# 2015_AlimBeaconEye.net
KiCad netlist of a schematic drawn in Altium Designer
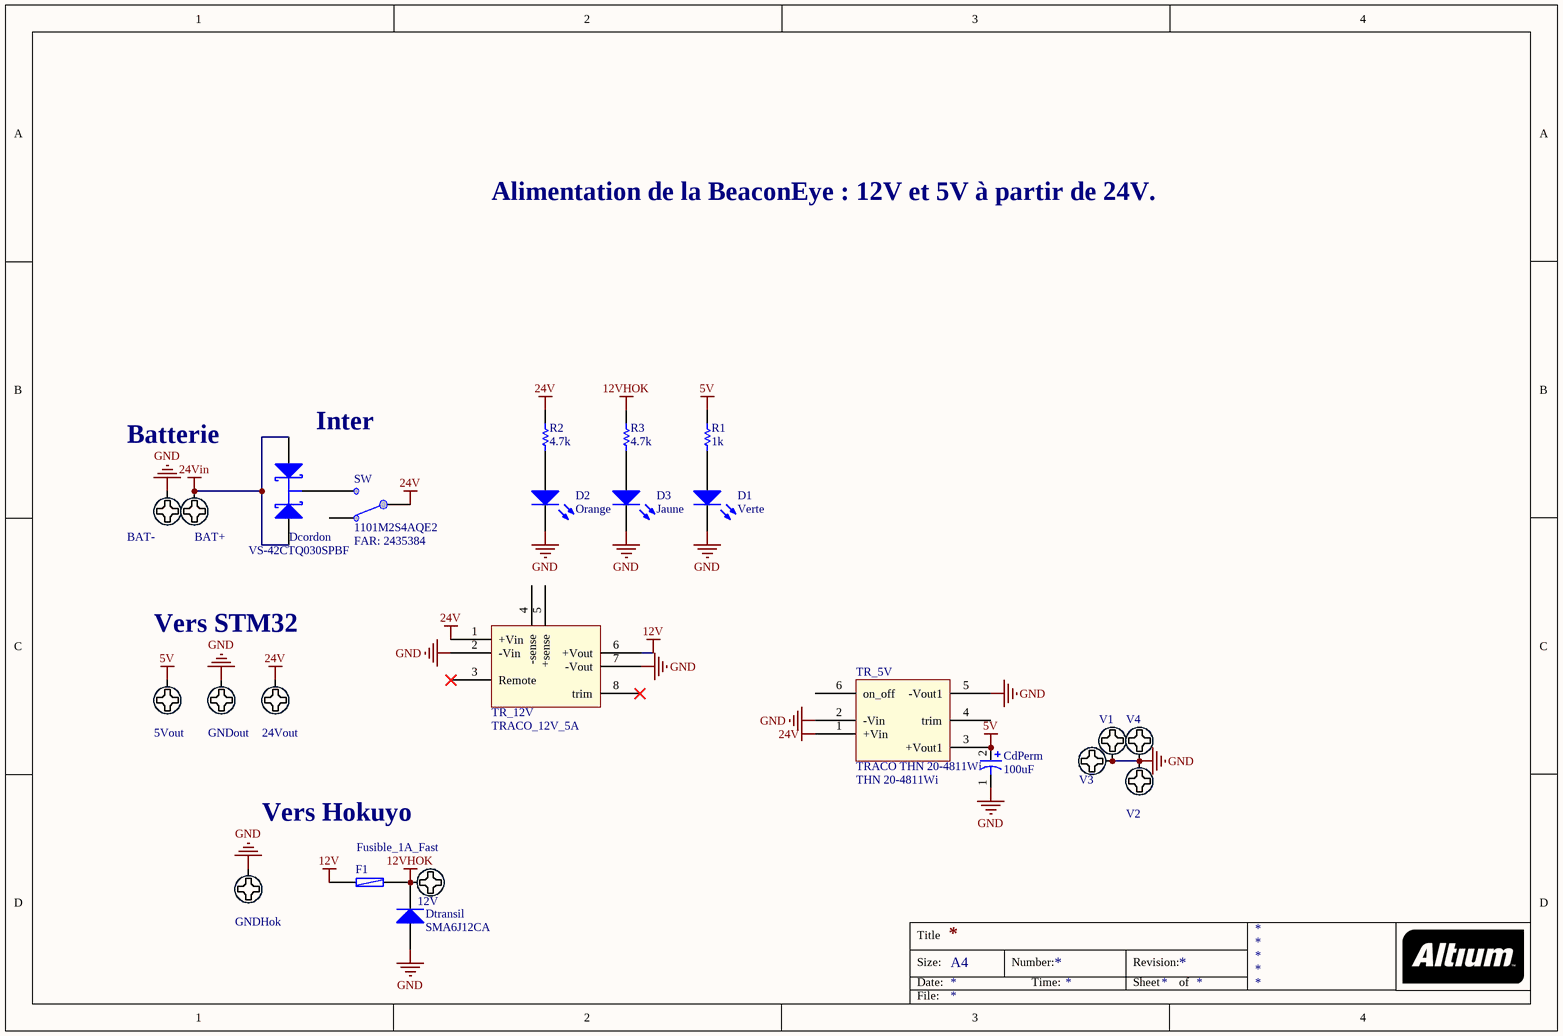
[diagram p0: 2015_AlimBeaconEye.SchDoc]

(export (version "E")
  (design (tool "Eeschema 10.0.6"))
  (components
    (comp (ref "5Vout")
      (value "Pad_M3")
      (footprint "M3x6mm")
      (description "Vis M3 X 6mm _TORX_Tête 6mm")
      (fields (field (name "PUBLISHER") "Damien Guitton"))
      (libsource (lib "_ROBOT") (part "Vis M3 X 6mm _TORX_Tête 6mm"))
    )
    (comp (ref "12V")
      (value "Pad_M3")
      (footprint "M3x6mm")
      (description "Vis M3 X 6mm _TORX_Tête 6mm")
      (fields (field (name "PUBLISHER") "Damien Guitton"))
      (libsource (lib "_ROBOT") (part "Vis M3 X 6mm _TORX_Tête 6mm"))
    )
    (comp (ref "24Vout")
      (value "Pad_M3")
      (footprint "M3x6mm")
      (description "Vis M3 X 6mm _TORX_Tête 6mm")
      (fields (field (name "PUBLISHER") "Damien Guitton"))
      (libsource (lib "_ROBOT") (part "Vis M3 X 6mm _TORX_Tête 6mm"))
    )
    (comp (ref "BAT+")
      (value "Pad_M3")
      (footprint "M3x6mm")
      (description "Vis M3 X 6mm _TORX_Tête 6mm")
      (fields (field (name "PUBLISHER") "Damien Guitton"))
      (libsource (lib "_ROBOT") (part "Vis M3 X 6mm _TORX_Tête 6mm"))
    )
    (comp (ref "BAT-")
      (value "Pad_M3")
      (footprint "M3x6mm")
      (description "Vis M3 X 6mm _TORX_Tête 6mm")
      (fields (field (name "PUBLISHER") "Damien Guitton"))
      (libsource (lib "_ROBOT") (part "Vis M3 X 6mm _TORX_Tête 6mm"))
    )
    (comp (ref "CdPerm")
      (value "100uF")
      (footprint "CONDENSATEUR_POLARISE_ELECTROLYTIQUE_RADIAL_5.08/8.9")
      (description "Polarized Capacitor")
      (libsource (lib "_ROBOT") (part "Condensateur Polarise Traversant"))
    )
    (comp (ref "D1")
      (value "Verte")
      (footprint "LED_0805")
      (description "Typical LED")
      (fields (field (name "PUBLISHER") "Altium Limited"))
      (libsource (lib "_ROBOT") (part "LED"))
    )
    (comp (ref "D2")
      (value "Orange")
      (footprint "LED_0805")
      (description "Typical LED")
      (fields (field (name "PUBLISHER") "Altium Limited"))
      (libsource (lib "_ROBOT") (part "LED"))
    )
    (comp (ref "D3")
      (value "Jaune")
      (footprint "LED_0805")
      (description "Typical LED")
      (fields (field (name "PUBLISHER") "Altium Limited"))
      (libsource (lib "_ROBOT") (part "LED"))
    )
    (comp (ref "Dcordon")
      (value "VS-42CTQ030SPBF")
      (footprint "D2Pak (123)")
      (description "DIODE SCHOTTKY DOUBLE")
      (fields (field (name "MANUFACTURER PART NUMBER") "BAT54C") (field (name "MANUFACTURER") "ZETEX"))
      (libsource (lib "_ROBOT") (part "Diode Shottky double BAT54C"))
    )
    (comp (ref "Dtransil")
      (value "SMA6J12CA")
      (footprint "DO214AC")
      (description "1 Amp General Purpose Rectifier")
      (fields (field (name "PUBLISHER") "Altium Limited"))
      (libsource (lib "Miscellaneous Devices") (part "Diode 1N4001"))
    )
    (comp (ref "F1")
      (value "Fusible_1A_Fast")
      (footprint "R0805_N")
      (description "Fuse")
      (fields (field (name "PUBLISHER") "Altium Limited"))
      (libsource (lib "DG_Fusible") (part "Fusible_SMD"))
    )
    (comp (ref "GNDHok")
      (value "Pad_M3")
      (footprint "M3x6mm")
      (description "Vis M3 X 6mm _TORX_Tête 6mm")
      (fields (field (name "PUBLISHER") "Damien Guitton"))
      (libsource (lib "_ROBOT") (part "Vis M3 X 6mm _TORX_Tête 6mm"))
    )
    (comp (ref "GNDout")
      (value "Pad_M3")
      (footprint "M3x6mm")
      (description "Vis M3 X 6mm _TORX_Tête 6mm")
      (fields (field (name "PUBLISHER") "Damien Guitton"))
      (libsource (lib "_ROBOT") (part "Vis M3 X 6mm _TORX_Tête 6mm"))
    )
    (comp (ref "R1")
      (value "1k")
      (footprint "R1206_N")
      (description "Resistor")
      (fields (field (name "PUBLISHER") "Altium Limited"))
      (libsource (lib "_ROBOT") (part "Resistor"))
    )
    (comp (ref "R2")
      (value "4.7k")
      (footprint "R1206_N")
      (description "Resistor")
      (fields (field (name "PUBLISHER") "Altium Limited"))
      (libsource (lib "_ROBOT") (part "Resistor"))
    )
    (comp (ref "R3")
      (value "4.7k")
      (footprint "R1206_N")
      (description "Resistor")
      (fields (field (name "PUBLISHER") "Altium Limited"))
      (libsource (lib "_ROBOT") (part "Resistor"))
    )
    (comp (ref "SW")
      (value "1101M2S4AQE2")
      (footprint "SW_UNIPOL_DROIT - APEM 18235")
      (description "Switch unipolaire a levier")
      (fields (field (name "FAR") "2435384"))
      (libsource (lib "_ROBOT") (part "SW SPDT- APEM Série 523x"))
    )
    (comp (ref "TR_5V")
      (value "TRACO THN 20-4811Wi")
      (footprint "TRACO_THN20")
      (description "Traco 20W 24V to 5V*4A")
      (fields (field (name "REF") "THN 20-4811Wi"))
      (libsource (lib "_ROBOT") (part "TRACO THN 20-4811Wi"))
    )
    (comp (ref "TR_12V")
      (value "TRACO_12V_5A")
      (footprint "TRACO_SIMPLE_12V_5A")
      (libsource (lib "_ROBOT") (part "TRACO_12V_5A"))
    )
    (comp (ref "V1")
      (value "Pad_M3")
      (footprint "M3x6mm")
      (description "Vis M3 X 6mm _TORX_Tête 6mm")
      (fields (field (name "PUBLISHER") "Damien Guitton"))
      (libsource (lib "_ROBOT") (part "Vis M3 X 6mm _TORX_Tête 6mm"))
    )
    (comp (ref "V2")
      (value "Pad_M3")
      (footprint "M3x6mm")
      (description "Vis M3 X 6mm _TORX_Tête 6mm")
      (fields (field (name "PUBLISHER") "Damien Guitton"))
      (libsource (lib "_ROBOT") (part "Vis M3 X 6mm _TORX_Tête 6mm"))
    )
    (comp (ref "V3")
      (value "Pad_M3")
      (footprint "M3x6mm")
      (description "Vis M3 X 6mm _TORX_Tête 6mm")
      (fields (field (name "PUBLISHER") "Damien Guitton"))
      (libsource (lib "_ROBOT") (part "Vis M3 X 6mm _TORX_Tête 6mm"))
    )
    (comp (ref "V4")
      (value "Pad_M3")
      (footprint "M3x6mm")
      (description "Vis M3 X 6mm _TORX_Tête 6mm")
      (fields (field (name "PUBLISHER") "Damien Guitton"))
      (libsource (lib "_ROBOT") (part "Vis M3 X 6mm _TORX_Tête 6mm"))
    )
  )
  (nets
    (net (code "1") (name "5V") (class "Default")
      (node (ref "5Vout") (pin "1") (pinfunction "1_1") (pintype "passive"))
      (node (ref "CdPerm") (pin "2") (pinfunction "2_2") (pintype "passive"))
      (node (ref "R1") (pin "1") (pinfunction "1_1") (pintype "passive"))
      (node (ref "TR_5V") (pin "3") (pinfunction "+Vout1_3") (pintype "passive"))
    )
    (net (code "2") (name "12V") (class "Default")
      (node (ref "F1") (pin "1") (pinfunction "1_1") (pintype "passive"))
      (node (ref "TR_12V") (pin "6") (pinfunction "+Vout_6") (pintype "passive"))
    )
    (net (code "3") (name "12VHOK") (class "Default")
      (node (ref "12V") (pin "1") (pinfunction "1_1") (pintype "passive"))
      (node (ref "Dtransil") (pin "2") (pinfunction "K_2") (pintype "passive"))
      (node (ref "F1") (pin "2") (pinfunction "2_2") (pintype "passive"))
      (node (ref "R3") (pin "1") (pinfunction "1_1") (pintype "passive"))
    )
    (net (code "4") (name "24V") (class "Default")
      (node (ref "24Vout") (pin "1") (pinfunction "1_1") (pintype "passive"))
      (node (ref "R2") (pin "1") (pinfunction "1_1") (pintype "passive"))
      (node (ref "SW") (pin "COMMON1") (pinfunction "COMMON1_COMMON1") (pintype "passive"))
      (node (ref "TR_12V") (pin "1") (pinfunction "+Vin_1") (pintype "passive"))
      (node (ref "TR_5V") (pin "1") (pinfunction "+Vin_1") (pintype "passive"))
    )
    (net (code "5") (name "24Vin") (class "Default")
      (node (ref "BAT+") (pin "1") (pinfunction "1_1") (pintype "passive"))
      (node (ref "Dcordon") (pin "1") (pinfunction "A1_1") (pintype "passive"))
      (node (ref "Dcordon") (pin "3") (pinfunction "A2_3") (pintype "passive"))
    )
    (net (code "6") (name "GND") (class "Default")
      (node (ref "BAT-") (pin "1") (pinfunction "1_1") (pintype "passive"))
      (node (ref "CdPerm") (pin "1") (pinfunction "1_1") (pintype "passive"))
      (node (ref "D1") (pin "2") (pinfunction "K_2") (pintype "passive"))
      (node (ref "D2") (pin "2") (pinfunction "K_2") (pintype "passive"))
      (node (ref "D3") (pin "2") (pinfunction "K_2") (pintype "passive"))
      (node (ref "Dtransil") (pin "1") (pinfunction "A_1") (pintype "passive"))
      (node (ref "GNDHok") (pin "1") (pinfunction "1_1") (pintype "passive"))
      (node (ref "GNDout") (pin "1") (pinfunction "1_1") (pintype "passive"))
      (node (ref "TR_12V") (pin "2") (pinfunction "-Vin_2") (pintype "passive"))
      (node (ref "TR_12V") (pin "7") (pinfunction "-Vout_7") (pintype "passive"))
      (node (ref "TR_5V") (pin "2") (pinfunction "-Vin_2") (pintype "passive"))
      (node (ref "TR_5V") (pin "5") (pinfunction "-Vout1_5") (pintype "passive"))
      (node (ref "V1") (pin "1") (pinfunction "1_1") (pintype "passive"))
      (node (ref "V2") (pin "1") (pinfunction "1_1") (pintype "passive"))
      (node (ref "V3") (pin "1") (pinfunction "1_1") (pintype "passive"))
      (node (ref "V4") (pin "1") (pinfunction "1_1") (pintype "passive"))
    )
    (net (code "7") (name "Net-(D1-A)") (class "Default")
      (node (ref "D1") (pin "1") (pinfunction "A_1") (pintype "passive"))
      (node (ref "R1") (pin "2") (pinfunction "2_2") (pintype "passive"))
    )
    (net (code "8") (name "Net-(D2-A)") (class "Default")
      (node (ref "D2") (pin "1") (pinfunction "A_1") (pintype "passive"))
      (node (ref "R2") (pin "2") (pinfunction "2_2") (pintype "passive"))
    )
    (net (code "9") (name "Net-(D3-A)") (class "Default")
      (node (ref "D3") (pin "1") (pinfunction "A_1") (pintype "passive"))
      (node (ref "R3") (pin "2") (pinfunction "2_2") (pintype "passive"))
    )
    (net (code "10") (name "Net-(Dcordon-K)") (class "Default")
      (node (ref "Dcordon") (pin "2") (pinfunction "K_2") (pintype "passive"))
      (node (ref "SW") (pin "NO1") (pinfunction "NO1_NO1") (pintype "passive"))
    )
    (net (code "11") (name "unconnected-(SW-PadNC1)") (class "Default")
      (node (ref "SW") (pin "NC1") (pinfunction "NC1_NC1") (pintype "passive"))
    )
    (net (code "12") (name "unconnected-(TR_5V-on_off-Pad6)") (class "Default")
      (node (ref "TR_5V") (pin "6") (pinfunction "on_off_6") (pintype "passive"))
    )
    (net (code "13") (name "unconnected-(TR_5V-trim-Pad4)") (class "Default")
      (node (ref "TR_5V") (pin "4") (pinfunction "trim_4") (pintype "passive"))
    )
    (net (code "14") (name "unconnected-(TR_12V-+sense-Pad5)") (class "Default")
      (node (ref "TR_12V") (pin "5") (pinfunction "+sense_5") (pintype "passive"))
    )
    (net (code "15") (name "unconnected-(TR_12V--sense-Pad4)") (class "Default")
      (node (ref "TR_12V") (pin "4") (pinfunction "-sense_4") (pintype "passive"))
    )
    (net (code "16") (name "unconnected-(TR_12V-Remote-Pad3)") (class "Default")
      (node (ref "TR_12V") (pin "3") (pinfunction "Remote_3") (pintype "passive+no_connect"))
    )
    (net (code "17") (name "unconnected-(TR_12V-trim-Pad8)") (class "Default")
      (node (ref "TR_12V") (pin "8") (pinfunction "trim_8") (pintype "passive"))
    )
  )
)
